# mcu.net
KiCad netlist of a schematic drawn in Altium Designer
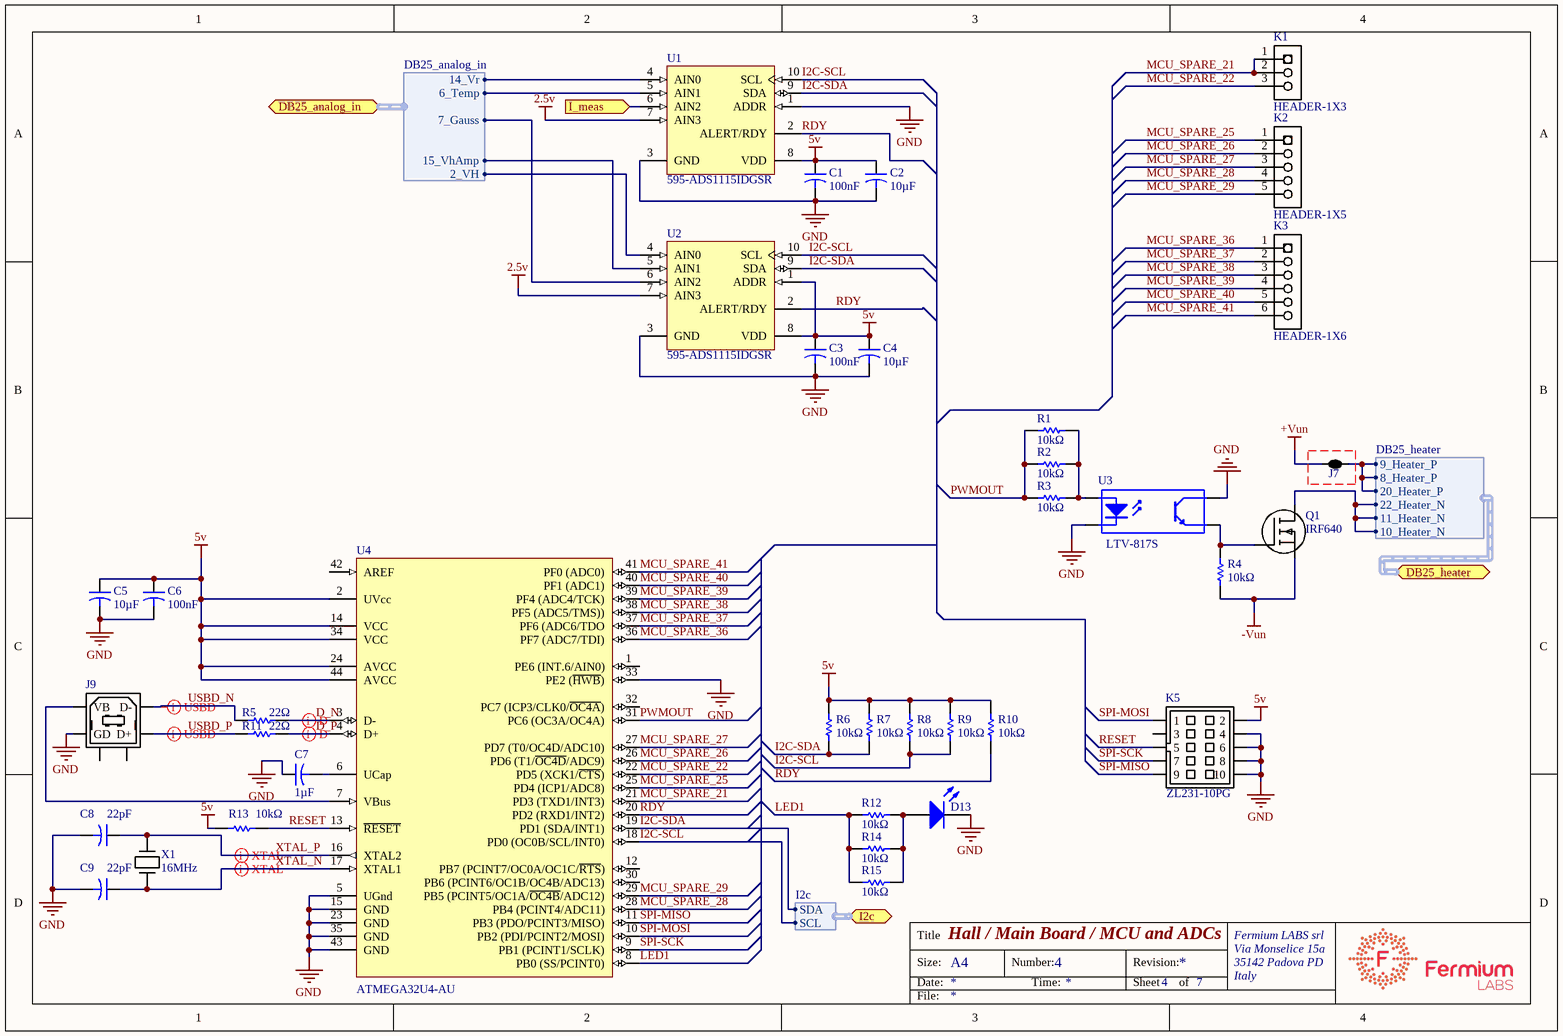
[diagram p0: mcu.SchDoc]

(export (version "E")
  (design (tool "Eeschema 10.0.6"))
  (components
    (comp (ref "C1")
      (value "~")
      (footprint "Passives:CAP 0805/2012")
      (description "Capacitor")
      (fields
        (field (name "CAPACITANCE") "100nF")
        (field (name "MANUFACTURER") "YAGEO")
        (field (name "MANUFACTURER PART NUMBER") "CC0805JRX7R9BB104")
      )
      (libsource (lib "Miscellaneous Devices") (part "Cap2"))
    )
    (comp (ref "C2")
      (value "~")
      (footprint "Passives:CAP 1206/3216")
      (description "Capacitor")
      (fields
        (field (name "MANUFACTURER") "SAMSUNG")
        (field (name "MANUFACTURER PART NUMBER") "CL31A106KAHNNNE")
        (field (name "CAPACITANCE") "10µF")
        (field (name "PUBLISHER") "Altium Limited")
      )
      (libsource (lib "Miscellaneous Devices") (part "Cap2"))
    )
    (comp (ref "C3")
      (value "~")
      (footprint "Passives:CAP 0805/2012")
      (description "Capacitor")
      (fields
        (field (name "CAPACITANCE") "100nF")
        (field (name "MANUFACTURER") "YAGEO")
        (field (name "MANUFACTURER PART NUMBER") "CC0805JRX7R9BB104")
      )
      (libsource (lib "Miscellaneous Devices") (part "Cap2"))
    )
    (comp (ref "C4")
      (value "~")
      (footprint "Passives:CAP 1206/3216")
      (description "Capacitor")
      (fields
        (field (name "MANUFACTURER") "SAMSUNG")
        (field (name "MANUFACTURER PART NUMBER") "CL31A106KAHNNNE")
        (field (name "CAPACITANCE") "10µF")
        (field (name "PUBLISHER") "Altium Limited")
      )
      (libsource (lib "Miscellaneous Devices") (part "Cap2"))
    )
    (comp (ref "C5")
      (value "~")
      (footprint "Passives:CAP 1206/3216")
      (description "Capacitor")
      (fields
        (field (name "MANUFACTURER") "SAMSUNG")
        (field (name "MANUFACTURER PART NUMBER") "CL31A106KAHNNNE")
        (field (name "CAPACITANCE") "10µF")
        (field (name "PUBLISHER") "Altium Limited")
      )
      (libsource (lib "Miscellaneous Devices") (part "Cap2"))
    )
    (comp (ref "C6")
      (value "~")
      (footprint "Passives:CAP 0805/2012")
      (description "Capacitor")
      (fields
        (field (name "CAPACITANCE") "100nF")
        (field (name "MANUFACTURER") "YAGEO")
        (field (name "MANUFACTURER PART NUMBER") "CC0805JRX7R9BB104")
      )
      (libsource (lib "Miscellaneous Devices") (part "Cap2"))
    )
    (comp (ref "C7")
      (value "~")
      (footprint "Passives:CAP 0805/2012")
      (description "Capacitor")
      (fields
        (field (name "MANUFACTURER") "SAMSUNG")
        (field (name "MANUFACTURER PART NUMBER") "CL21B105KAFNNNE")
        (field (name "CAPACITANCE") "1µF")
        (field (name "PUBLISHER") "Altium Limited")
      )
      (libsource (lib "Miscellaneous Devices") (part "Cap2"))
    )
    (comp (ref "C8")
      (value "~")
      (footprint "Passives:CAP 0805/2012")
      (description "Capacitor")
      (fields
        (field (name "MANUFACTURER") "SAMSUNG")
        (field (name "MANUFACTURER PART NUMBER") "CL21C220JBANNNC")
        (field (name "CAPACITANCE") "22pF")
        (field (name "PUBLISHER") "Altium Limited")
      )
      (libsource (lib "Miscellaneous Devices") (part "Cap2"))
    )
    (comp (ref "C9")
      (value "~")
      (footprint "Passives:CAP 0805/2012")
      (description "Capacitor")
      (fields
        (field (name "MANUFACTURER") "SAMSUNG")
        (field (name "MANUFACTURER PART NUMBER") "CL21C220JBANNNC")
        (field (name "CAPACITANCE") "22pF")
        (field (name "PUBLISHER") "Altium Limited")
      )
      (libsource (lib "Miscellaneous Devices") (part "Cap2"))
    )
    (comp (ref "D13")
      (value "~")
      (footprint "LED-0")
      (description "LED red 5mm")
      (fields
        (field (name "MANUFACTURER") "KINGBRIGHT ELECTRONIC")
        (field (name "MANUFACTURER PART NUMBER") "L-1503CB/1ID")
      )
      (libsource (lib "Miscellaneous Devices") (part "LED0"))
    )
    (comp (ref "J7")
      (value "2 way net tie junction")
      (footprint "2way_LP")
      (libsource (lib "NetTieLib") (part "2way"))
    )
    (comp (ref "J9")
      (value "~")
      (footprint "USB_TypeB")
      (description "USB b device connector")
      (fields (field (name "MANUFACTURER") "LUMBERG") (field (name "MANUFACTURER PART NUMBER") "2411 02"))
      (libsource (lib "TH Connectors") (part "USB-B"))
    )
    (comp (ref "K1")
      (value "HEADER-1X3")
      (footprint "HEADER-1X3")
      (libsource (lib "TH Connectors") (part "HEADER-1X3"))
    )
    (comp (ref "K2")
      (value "HEADER-1X5")
      (footprint "HEADER-1X5")
      (description "PINHEADER 1X5")
      (libsource (lib "TH Connectors") (part "HEADER-1X5"))
    )
    (comp (ref "K3")
      (value "HEADER-1X6")
      (footprint "HEADER-1X6")
      (libsource (lib "TH Connectors") (part "HEADER-1X6"))
    )
    (comp (ref "K5")
      (value "~")
      (footprint "IDC10-B")
      (description "header 10pin, boxed")
      (fields
        (field (name "SUPPLIER PART NUMBER 1") "ZL231-10PG")
        (field (name "MANUFACTURER") "NINIGI")
        (field (name "MANUFACTURER PART NUMBER") "ZL231-10PG")
      )
      (libsource (lib "vh_altium_library") (part "IDC10"))
    )
    (comp (ref "Q1")
      (value "IRF640")
      (footprint "vh_altium_library:DPAK-GDS")
      (description "N CHANNEL MOSFET")
      (fields (field (name "MANUFACTURER PART NUMBER") "IRF640NSPBF"))
      (libsource (lib "vh_altium_library") (part "IRLML2502"))
    )
    (comp (ref "R1")
      (value "~")
      (footprint "Passives:RES 0805/2012")
      (description "Resistor")
      (fields
        (field (name "MANUFACTURER") "YAGEO")
        (field (name "MANUFACTURER PART NUMBER") "RC0805JR-0710KL")
        (field (name "RESISTANCE") "10kΩ")
        (field (name "PUBLISHER") "Altium Limited")
      )
      (libsource (lib "Miscellaneous Devices") (part "Res1"))
    )
    (comp (ref "R2")
      (value "~")
      (footprint "Passives:RES 0805/2012")
      (description "Resistor")
      (fields
        (field (name "MANUFACTURER") "YAGEO")
        (field (name "MANUFACTURER PART NUMBER") "RC0805JR-0710KL")
        (field (name "RESISTANCE") "10kΩ")
        (field (name "PUBLISHER") "Altium Limited")
      )
      (libsource (lib "Miscellaneous Devices") (part "Res1"))
    )
    (comp (ref "R3")
      (value "~")
      (footprint "Passives:RES 0805/2012")
      (description "Resistor")
      (fields
        (field (name "MANUFACTURER") "YAGEO")
        (field (name "MANUFACTURER PART NUMBER") "RC0805JR-0710KL")
        (field (name "RESISTANCE") "10kΩ")
        (field (name "PUBLISHER") "Altium Limited")
      )
      (libsource (lib "Miscellaneous Devices") (part "Res1"))
    )
    (comp (ref "R4")
      (value "~")
      (footprint "Passives:RES 0805/2012")
      (description "Resistor")
      (fields
        (field (name "MANUFACTURER") "YAGEO")
        (field (name "MANUFACTURER PART NUMBER") "RC0805JR-0710KL")
        (field (name "RESISTANCE") "10kΩ")
        (field (name "PUBLISHER") "Altium Limited")
      )
      (libsource (lib "Miscellaneous Devices") (part "Res1"))
    )
    (comp (ref "R5")
      (value "~")
      (footprint "Passives:RES 0805/2012")
      (description "Resistor")
      (fields
        (field (name "RESISTANCE") "22Ω")
        (field (name "MANUFACTURER") "ROYAL OHM")
        (field (name "MANUFACTURER PART NUMBER") "0805S8F220JT5E")
      )
      (libsource (lib "Miscellaneous Devices") (part "Res1"))
    )
    (comp (ref "R6")
      (value "~")
      (footprint "Passives:RES 0805/2012")
      (description "Resistor")
      (fields
        (field (name "MANUFACTURER") "YAGEO")
        (field (name "MANUFACTURER PART NUMBER") "RC0805JR-0710KL")
        (field (name "RESISTANCE") "10kΩ")
        (field (name "PUBLISHER") "Altium Limited")
      )
      (libsource (lib "Miscellaneous Devices") (part "Res1"))
    )
    (comp (ref "R7")
      (value "~")
      (footprint "Passives:RES 0805/2012")
      (description "Resistor")
      (fields
        (field (name "MANUFACTURER") "YAGEO")
        (field (name "MANUFACTURER PART NUMBER") "RC0805JR-0710KL")
        (field (name "RESISTANCE") "10kΩ")
        (field (name "PUBLISHER") "Altium Limited")
      )
      (libsource (lib "Miscellaneous Devices") (part "Res1"))
    )
    (comp (ref "R8")
      (value "~")
      (footprint "Passives:RES 0805/2012")
      (description "Resistor")
      (fields
        (field (name "MANUFACTURER") "YAGEO")
        (field (name "MANUFACTURER PART NUMBER") "RC0805JR-0710KL")
        (field (name "RESISTANCE") "10kΩ")
        (field (name "PUBLISHER") "Altium Limited")
      )
      (libsource (lib "Miscellaneous Devices") (part "Res1"))
    )
    (comp (ref "R9")
      (value "~")
      (footprint "Passives:RES 0805/2012")
      (description "Resistor")
      (fields
        (field (name "MANUFACTURER") "YAGEO")
        (field (name "MANUFACTURER PART NUMBER") "RC0805JR-0710KL")
        (field (name "RESISTANCE") "10kΩ")
        (field (name "PUBLISHER") "Altium Limited")
      )
      (libsource (lib "Miscellaneous Devices") (part "Res1"))
    )
    (comp (ref "R10")
      (value "~")
      (footprint "Passives:RES 0805/2012")
      (description "Resistor")
      (fields
        (field (name "MANUFACTURER") "YAGEO")
        (field (name "MANUFACTURER PART NUMBER") "RC0805JR-0710KL")
        (field (name "RESISTANCE") "10kΩ")
        (field (name "PUBLISHER") "Altium Limited")
      )
      (libsource (lib "Miscellaneous Devices") (part "Res1"))
    )
    (comp (ref "R11")
      (value "~")
      (footprint "Passives:RES 0805/2012")
      (description "Resistor")
      (fields
        (field (name "RESISTANCE") "22Ω")
        (field (name "MANUFACTURER") "ROYAL OHM")
        (field (name "MANUFACTURER PART NUMBER") "0805S8F220JT5E")
      )
      (libsource (lib "Miscellaneous Devices") (part "Res1"))
    )
    (comp (ref "R12")
      (value "~")
      (footprint "Passives:RES 0805/2012")
      (description "Resistor")
      (fields
        (field (name "MANUFACTURER") "YAGEO")
        (field (name "MANUFACTURER PART NUMBER") "RC0805JR-0710KL")
        (field (name "RESISTANCE") "10kΩ")
        (field (name "PUBLISHER") "Altium Limited")
      )
      (libsource (lib "Miscellaneous Devices") (part "Res1"))
    )
    (comp (ref "R13")
      (value "Res1")
      (footprint "Passives:RES 0805/2012")
      (description "Resistor")
      (fields
        (field (name "MANUFACTURER") "YAGEO")
        (field (name "MANUFACTURER PART NUMBER") "RC0805JR-0710KL")
        (field (name "RESISTANCE") "10kΩ")
        (field (name "PUBLISHER") "Altium Limited")
      )
      (libsource (lib "Miscellaneous Devices") (part "Res1"))
    )
    (comp (ref "R14")
      (value "~")
      (footprint "Passives:RES 0805/2012")
      (description "Resistor")
      (fields
        (field (name "MANUFACTURER") "YAGEO")
        (field (name "MANUFACTURER PART NUMBER") "RC0805JR-0710KL")
        (field (name "RESISTANCE") "10kΩ")
        (field (name "PUBLISHER") "Altium Limited")
      )
      (libsource (lib "Miscellaneous Devices") (part "Res1"))
    )
    (comp (ref "R15")
      (value "~")
      (footprint "Passives:RES 0805/2012")
      (description "Resistor")
      (fields
        (field (name "MANUFACTURER") "YAGEO")
        (field (name "MANUFACTURER PART NUMBER") "RC0805JR-0710KL")
        (field (name "RESISTANCE") "10kΩ")
        (field (name "PUBLISHER") "Altium Limited")
      )
      (libsource (lib "Miscellaneous Devices") (part "Res1"))
    )
    (comp (ref "U1")
      (value "~")
      (footprint "TI-DGS10_N")
      (description "16-Bit 4 channel ADC with PGA and reference")
      (fields
        (field (name "SUPPLIER PART NUMBER 1") "595-ADS1115IDGSR")
        (field (name "MANUFACTURER") "Texas Instruments")
        (field (name "MANUFACTURER PART NUMBER") "ADS1115IDGSR")
      )
      (libsource (lib "TI Data Converters Analog to Digital Converter") (part "ADS1115IDGSR"))
    )
    (comp (ref "U2")
      (value "~")
      (footprint "TI-DGS10_N")
      (description "16-Bit 4 channel ADC with PGA and reference")
      (fields
        (field (name "SUPPLIER PART NUMBER 1") "595-ADS1115IDGSR")
        (field (name "MANUFACTURER") "Texas Instruments")
        (field (name "MANUFACTURER PART NUMBER") "ADS1115IDGSR")
      )
      (libsource (lib "TI Data Converters Analog to Digital Converter") (part "ADS1115IDGSR"))
    )
    (comp (ref "U3")
      (value "LTV-817")
      (footprint "custom_components:gullwing-opto-4")
      (description "4-Pin Phototransistor Optocoupler")
      (fields
        (field (name "SUPPLIER PART NUMBER 1") "LTV-817S")
        (field (name "MANUFACTURER") "LITEON")
        (field (name "MANUFACTURER PART NUMBER") "LTV-817S")
        (field (name "PUBLISHER") "Altium Limited")
      )
      (libsource (lib "Miscellaneous Devices") (part "Optoisolator1"))
    )
    (comp (ref "U4")
      (value "~")
      (footprint "44ML_N")
      (description "8-bit AVR MCU, 16MHz, 32KB Flash, 1KB EEPROM, 2.5KB SRAM, USB")
      (fields (field (name "MANUFACTURER") "ATMEL") (field (name "MANUFACTURER PART NUMBER") "ATMEGA32U4-AU"))
      (libsource (lib "Atmel Microcontroller megaAVR") (part "ATmega32U4-AU"))
    )
    (comp (ref "X1")
      (value "~")
      (footprint "ABRACON ABLS")
      (description "quartz crystal")
      (fields
        (field (name "MANUFACTURER") "YIC")
        (field (name "FREQUENCY") "16MHz")
        (field (name "POWER") "1mW")
      )
      (libsource (lib "vh_altium_library") (part "CRYSTAL-GENERIC"))
    )
  )
  (nets
    (net (code "4") (name "+Vun") (class "Default")
      (node (ref "J7") (pin "1") (pinfunction "1_1") (pintype "passive"))
    )
    (net (code "5") (name "-Vun") (class "Default")
      (node (ref "Q1") (pin "S") (pintype "passive"))
      (node (ref "R4") (pin "1") (pinfunction "1_1") (pintype "passive"))
    )
    (net (code "6") (name "/2_VH") (class "Default")
      (node (ref "U2") (pin "4") (pinfunction "AIN0_4") (pintype "input"))
    )
    (net (code "7") (name "/6_Temp") (class "Default")
      (node (ref "U1") (pin "5") (pinfunction "AIN1_5") (pintype "input"))
    )
    (net (code "8") (name "/7_Gauss") (class "Default")
      (node (ref "U2") (pin "6") (pinfunction "AIN2_6") (pintype "input"))
    )
    (net (code "9") (name "/10_Heater_N") (class "Default") (node (ref "Q1") (pin "D") (pintype "passive")))
    (net (code "10") (name "/14_Vr") (class "Default")
      (node (ref "U1") (pin "4") (pinfunction "AIN0_4") (pintype "input"))
    )
    (net (code "11") (name "/15_VhAmp") (class "Default")
      (node (ref "U2") (pin "5") (pinfunction "AIN1_5") (pintype "input"))
    )
    (net (code "12") (name "/20_Heater_P") (class "Default")
      (node (ref "J7") (pin "2") (pinfunction "2_2") (pintype "passive"))
    )
    (net (code "13") (name "/D_N") (class "Default")
      (node (ref "R5") (pin "1") (pinfunction "1_1") (pintype "passive"))
      (node (ref "U4") (pin "3") (pinfunction "D-_3") (pintype "bidirectional"))
    )
    (net (code "14") (name "/D_P") (class "Default")
      (node (ref "R11") (pin "1") (pinfunction "1_1") (pintype "passive"))
      (node (ref "U4") (pin "4") (pinfunction "D+_4") (pintype "bidirectional"))
    )
    (net (code "15") (name "/I2C-SCL") (class "Default")
      (node (ref "R8") (pin "1") (pinfunction "1_1") (pintype "passive"))
      (node (ref "R9") (pin "1") (pinfunction "1_1") (pintype "passive"))
      (node (ref "U1") (pin "10") (pinfunction "SCL_10") (pintype "input"))
      (node (ref "U2") (pin "10") (pinfunction "SCL_10") (pintype "input"))
      (node (ref "U4") (pin "18") (pinfunction "PD0_(OC0B/SCL/INT0)_18") (pintype "bidirectional"))
    )
    (net (code "16") (name "/I2C-SDA") (class "Default")
      (node (ref "R6") (pin "1") (pinfunction "1_1") (pintype "passive"))
      (node (ref "R7") (pin "1") (pinfunction "1_1") (pintype "passive"))
      (node (ref "U1") (pin "9") (pinfunction "SDA_9") (pintype "bidirectional"))
      (node (ref "U2") (pin "9") (pinfunction "SDA_9") (pintype "bidirectional"))
      (node (ref "U4") (pin "19") (pinfunction "PD1_(SDA/INT1)_19") (pintype "bidirectional"))
    )
    (net (code "17") (name "/I_meas") (class "Default")
      (node (ref "U1") (pin "6") (pinfunction "AIN2_6") (pintype "input"))
    )
    (net (code "18") (name "/LED1") (class "Default")
      (node (ref "R12") (pin "2") (pinfunction "2_2") (pintype "passive"))
      (node (ref "R14") (pin "2") (pinfunction "2_2") (pintype "passive"))
      (node (ref "R15") (pin "2") (pinfunction "2_2") (pintype "passive"))
      (node (ref "U4") (pin "8") (pinfunction "PB0_(SS/PCINT0)_8") (pintype "bidirectional"))
    )
    (net (code "19") (name "/MCU_SPARE_21") (class "Default")
      (node (ref "K1") (pin "1") (pintype "passive"))
      (node (ref "K1") (pin "2") (pintype "passive"))
      (node (ref "U4") (pin "21") (pinfunction "PD3_(TXD1/INT3)_21") (pintype "bidirectional"))
    )
    (net (code "20") (name "/MCU_SPARE_22") (class "Default")
      (node (ref "K1") (pin "3") (pintype "passive"))
      (node (ref "U4") (pin "22") (pinfunction "PD5_(XCK1/~{CTS})_22") (pintype "bidirectional"))
    )
    (net (code "21") (name "/MCU_SPARE_25") (class "Default")
      (node (ref "K2") (pin "1") (pintype "passive"))
      (node (ref "U4") (pin "25") (pinfunction "PD4_(ICP1/ADC8)_25") (pintype "bidirectional"))
    )
    (net (code "22") (name "/MCU_SPARE_26") (class "Default")
      (node (ref "K2") (pin "2") (pintype "passive"))
      (node (ref "U4") (pin "26") (pinfunction "PD6_(T1/~{OC4D}/ADC9)_26") (pintype "bidirectional"))
    )
    (net (code "23") (name "/MCU_SPARE_27") (class "Default")
      (node (ref "K2") (pin "3") (pintype "passive"))
      (node (ref "U4") (pin "27") (pinfunction "PD7_(T0/OC4D/ADC10)_27") (pintype "bidirectional"))
    )
    (net (code "24") (name "/MCU_SPARE_28") (class "Default")
      (node (ref "K2") (pin "4") (pintype "passive"))
      (node (ref "U4") (pin "28") (pinfunction "PB4_(PCINT4/ADC11)_28") (pintype "bidirectional"))
    )
    (net (code "25") (name "/MCU_SPARE_29") (class "Default")
      (node (ref "K2") (pin "5") (pintype "passive"))
      (node (ref "U4") (pin "29") (pinfunction "PB5_(PCINT5/OC1A/~{OC4B}/ADC12)_29") (pintype "bidirectional"))
    )
    (net (code "26") (name "/MCU_SPARE_36") (class "Default")
      (node (ref "K3") (pin "1") (pintype "passive"))
      (node (ref "U4") (pin "36") (pinfunction "PF7_(ADC7/TDI)_36") (pintype "bidirectional"))
    )
    (net (code "27") (name "/MCU_SPARE_37") (class "Default")
      (node (ref "K3") (pin "2") (pintype "passive"))
      (node (ref "U4") (pin "37") (pinfunction "PF6_(ADC6/TDO_37") (pintype "bidirectional"))
    )
    (net (code "28") (name "/MCU_SPARE_38") (class "Default")
      (node (ref "K3") (pin "3") (pintype "passive"))
      (node (ref "U4") (pin "38") (pinfunction "PF5_(ADC5/TMS))_38") (pintype "bidirectional"))
    )
    (net (code "29") (name "/MCU_SPARE_39") (class "Default")
      (node (ref "K3") (pin "4") (pintype "passive"))
      (node (ref "U4") (pin "39") (pinfunction "PF4_(ADC4/TCK)_39") (pintype "bidirectional"))
    )
    (net (code "30") (name "/MCU_SPARE_40") (class "Default")
      (node (ref "K3") (pin "5") (pintype "passive"))
      (node (ref "U4") (pin "40") (pinfunction "PF1_(ADC1)_40") (pintype "bidirectional"))
    )
    (net (code "31") (name "/MCU_SPARE_41") (class "Default")
      (node (ref "K3") (pin "6") (pintype "passive"))
      (node (ref "U4") (pin "41") (pinfunction "PF0_(ADC0)_41") (pintype "bidirectional"))
    )
    (net (code "32") (name "/PWMOUT") (class "Default")
      (node (ref "R1") (pin "2") (pinfunction "2_2") (pintype "passive"))
      (node (ref "R2") (pin "2") (pinfunction "2_2") (pintype "passive"))
      (node (ref "R3") (pin "2") (pinfunction "2_2") (pintype "passive"))
      (node (ref "U4") (pin "31") (pinfunction "PC6_(OC3A/OC4A)_31") (pintype "bidirectional"))
    )
    (net (code "33") (name "/RDY") (class "Default")
      (node (ref "R10") (pin "1") (pinfunction "1_1") (pintype "passive"))
      (node (ref "U1") (pin "2") (pinfunction "ALERT/RDY_2") (pintype "open_collector"))
      (node (ref "U2") (pin "2") (pinfunction "ALERT/RDY_2") (pintype "open_collector"))
      (node (ref "U4") (pin "20") (pinfunction "PD2_(RXD1/INT2)_20") (pintype "bidirectional"))
    )
    (net (code "34") (name "/RESET") (class "Default")
      (node (ref "K5") (pin "5") (pinfunction "5_5") (pintype "passive"))
      (node (ref "R13") (pin "1") (pinfunction "1_1") (pintype "passive"))
      (node (ref "U4") (pin "13") (pinfunction "~{RESET}_13") (pintype "input"))
    )
    (net (code "35") (name "/SPI-MISO") (class "Default")
      (node (ref "K5") (pin "9") (pinfunction "9_9") (pintype "passive"))
      (node (ref "U4") (pin "11") (pinfunction "PB3_(PDO/PCINT3/MISO)_11") (pintype "bidirectional"))
    )
    (net (code "36") (name "/SPI-MOSI") (class "Default")
      (node (ref "K5") (pin "1") (pinfunction "1_1") (pintype "passive"))
      (node (ref "U4") (pin "10") (pinfunction "PB2_(PDI/PCINT2/MOSI)_10") (pintype "bidirectional"))
    )
    (net (code "37") (name "/SPI-SCK") (class "Default")
      (node (ref "K5") (pin "7") (pinfunction "7_7") (pintype "passive"))
      (node (ref "U4") (pin "9") (pinfunction "PB1_(PCINT1/SCLK)_9") (pintype "bidirectional"))
    )
    (net (code "38") (name "/USBD_N") (class "Default")
      (node (ref "J9") (pin "2") (pinfunction "D-_2") (pintype "passive"))
      (node (ref "R5") (pin "2") (pinfunction "2_2") (pintype "passive"))
    )
    (net (code "39") (name "/USBD_P") (class "Default")
      (node (ref "J9") (pin "3") (pinfunction "D+_3") (pintype "passive"))
      (node (ref "R11") (pin "2") (pinfunction "2_2") (pintype "passive"))
    )
    (net (code "40") (name "/XTAL_N") (class "Default")
      (node (ref "C9") (pin "1") (pinfunction "1_1") (pintype "passive"))
      (node (ref "U4") (pin "17") (pinfunction "XTAL1_17") (pintype "input"))
      (node (ref "X1") (pin "2") (pintype "passive"))
    )
    (net (code "41") (name "/XTAL_P") (class "Default")
      (node (ref "C8") (pin "1") (pinfunction "1_1") (pintype "passive"))
      (node (ref "U4") (pin "16") (pinfunction "XTAL2_16") (pintype "output"))
      (node (ref "X1") (pin "1") (pintype "passive"))
    )
    (net (code "45") (name "2.5v") (class "Default")
      (node (ref "U1") (pin "7") (pinfunction "AIN3_7") (pintype "input"))
      (node (ref "U2") (pin "7") (pinfunction "AIN3_7") (pintype "input"))
    )
    (net (code "46") (name "5v") (class "Default")
      (node (ref "C1") (pin "1") (pinfunction "1_1") (pintype "passive"))
      (node (ref "C2") (pin "1") (pinfunction "1_1") (pintype "passive"))
      (node (ref "C3") (pin "1") (pinfunction "1_1") (pintype "passive"))
      (node (ref "C4") (pin "1") (pinfunction "1_1") (pintype "passive"))
      (node (ref "C5") (pin "1") (pinfunction "1_1") (pintype "passive"))
      (node (ref "C6") (pin "1") (pinfunction "1_1") (pintype "passive"))
      (node (ref "K5") (pin "2") (pinfunction "2_2") (pintype "passive"))
      (node (ref "R10") (pin "2") (pinfunction "2_2") (pintype "passive"))
      (node (ref "R13") (pin "2") (pinfunction "2_2") (pintype "passive"))
      (node (ref "R6") (pin "2") (pinfunction "2_2") (pintype "passive"))
      (node (ref "R7") (pin "2") (pinfunction "2_2") (pintype "passive"))
      (node (ref "R8") (pin "2") (pinfunction "2_2") (pintype "passive"))
      (node (ref "R9") (pin "2") (pinfunction "2_2") (pintype "passive"))
      (node (ref "U1") (pin "8") (pinfunction "VDD_8") (pintype "power_in"))
      (node (ref "U2") (pin "1") (pinfunction "ADDR_1") (pintype "input"))
      (node (ref "U2") (pin "8") (pinfunction "VDD_8") (pintype "power_in"))
      (node (ref "U4") (pin "14") (pinfunction "VCC_14") (pintype "power_in"))
      (node (ref "U4") (pin "2") (pinfunction "UVcc_2") (pintype "power_in"))
      (node (ref "U4") (pin "24") (pinfunction "AVCC_24") (pintype "power_in"))
      (node (ref "U4") (pin "34") (pinfunction "VCC_34") (pintype "power_in"))
      (node (ref "U4") (pin "44") (pinfunction "AVCC_44") (pintype "power_in"))
    )
    (net (code "47") (name "GND") (class "Default")
      (node (ref "C1") (pin "2") (pinfunction "2_2") (pintype "passive"))
      (node (ref "C2") (pin "2") (pinfunction "2_2") (pintype "passive"))
      (node (ref "C3") (pin "2") (pinfunction "2_2") (pintype "passive"))
      (node (ref "C4") (pin "2") (pinfunction "2_2") (pintype "passive"))
      (node (ref "C5") (pin "2") (pinfunction "2_2") (pintype "passive"))
      (node (ref "C6") (pin "2") (pinfunction "2_2") (pintype "passive"))
      (node (ref "C7") (pin "1") (pinfunction "1_1") (pintype "passive"))
      (node (ref "C8") (pin "2") (pinfunction "2_2") (pintype "passive"))
      (node (ref "C9") (pin "2") (pinfunction "2_2") (pintype "passive"))
      (node (ref "D13") (pin "1") (pinfunction "K_1") (pintype "passive"))
      (node (ref "J9") (pin "4") (pinfunction "GD_4") (pintype "passive"))
      (node (ref "K5") (pin "10") (pinfunction "10_10") (pintype "passive"))
      (node (ref "K5") (pin "4") (pinfunction "4_4") (pintype "passive"))
      (node (ref "K5") (pin "6") (pinfunction "6_6") (pintype "passive"))
      (node (ref "K5") (pin "8") (pinfunction "8_8") (pintype "passive"))
      (node (ref "U1") (pin "1") (pinfunction "ADDR_1") (pintype "input"))
      (node (ref "U1") (pin "3") (pinfunction "GND_3") (pintype "power_in"))
      (node (ref "U2") (pin "3") (pinfunction "GND_3") (pintype "power_in"))
      (node (ref "U3") (pin "2") (pinfunction "K_2") (pintype "passive"))
      (node (ref "U3") (pin "4") (pinfunction "C_4") (pintype "passive"))
      (node (ref "U4") (pin "15") (pinfunction "GND_15") (pintype "power_in"))
      (node (ref "U4") (pin "23") (pinfunction "GND_23") (pintype "power_in"))
      (node (ref "U4") (pin "33") (pinfunction "PE2_(~{HWB})_33") (pintype "bidirectional"))
      (node (ref "U4") (pin "35") (pinfunction "GND_35") (pintype "power_in"))
      (node (ref "U4") (pin "43") (pinfunction "GND_43") (pintype "power_in"))
      (node (ref "U4") (pin "5") (pinfunction "UGnd_5") (pintype "power_in"))
    )
    (net (code "48") (name "Net-(D13-A)") (class "Default")
      (node (ref "D13") (pin "2") (pinfunction "A_2") (pintype "passive"))
      (node (ref "R12") (pin "1") (pinfunction "1_1") (pintype "passive"))
      (node (ref "R14") (pin "1") (pinfunction "1_1") (pintype "passive"))
      (node (ref "R15") (pin "1") (pinfunction "1_1") (pintype "passive"))
    )
    (net (code "49") (name "Net-(J9-VB)") (class "Default")
      (node (ref "J9") (pin "1") (pinfunction "VB_1") (pintype "passive"))
      (node (ref "U4") (pin "7") (pinfunction "VBus_7") (pintype "input"))
    )
    (net (code "50") (name "Net-(U3-A)") (class "Default")
      (node (ref "R1") (pin "1") (pinfunction "1_1") (pintype "passive"))
      (node (ref "R2") (pin "1") (pinfunction "1_1") (pintype "passive"))
      (node (ref "R3") (pin "1") (pinfunction "1_1") (pintype "passive"))
      (node (ref "U3") (pin "1") (pinfunction "A_1") (pintype "passive"))
    )
    (net (code "51") (name "Net-(U3-E)") (class "Default")
      (node (ref "Q1") (pin "G") (pintype "passive"))
      (node (ref "R4") (pin "2") (pinfunction "2_2") (pintype "passive"))
      (node (ref "U3") (pin "3") (pinfunction "E_3") (pintype "passive"))
    )
    (net (code "52") (name "Net-(U4-UCap)") (class "Default")
      (node (ref "C7") (pin "2") (pinfunction "2_2") (pintype "passive"))
      (node (ref "U4") (pin "6") (pinfunction "UCap_6") (pintype "passive"))
    )
    (net (code "53") (name "unconnected-(J9-Pad5)") (class "Default")
      (node (ref "J9") (pin "5") (pintype "passive"))
    )
    (net (code "54") (name "unconnected-(J9-Pad6)") (class "Default")
      (node (ref "J9") (pin "6") (pintype "passive"))
    )
    (net (code "55") (name "unconnected-(K5-Pad3)") (class "Default")
      (node (ref "K5") (pin "3") (pinfunction "3_3") (pintype "passive"))
    )
    (net (code "56") (name "unconnected-(U4-AREF-Pad42)") (class "Default")
      (node (ref "U4") (pin "42") (pinfunction "AREF_42") (pintype "input"))
    )
    (net (code "57") (name "unconnected-(U4-PB6_(PCINT6{slash}OC1B{slash}OC4B{slash}ADC13)-Pad30)") (class "Default")
      (node (ref "U4") (pin "30") (pinfunction "PB6_(PCINT6/OC1B/OC4B/ADC13)_30") (pintype "bidirectional"))
    )
    (net (code "58") (name "unconnected-(U4-PB7_(PCINT7{slash}OC0A{slash}OC1C{slash}~{RTS})-Pad12)") (class "Default")
      (node (ref "U4") (pin "12") (pinfunction "PB7_(PCINT7/OC0A/OC1C/~{RTS})_12") (pintype "bidirectional"))
    )
    (net (code "59") (name "unconnected-(U4-PC7_(ICP3{slash}CLK0{slash}~{OC4A})-Pad32)") (class "Default")
      (node (ref "U4") (pin "32") (pinfunction "PC7_(ICP3/CLK0/~{OC4A})_32") (pintype "bidirectional"))
    )
    (net (code "60") (name "unconnected-(U4-PE6_(INT.6{slash}AIN0)-Pad1)") (class "Default")
      (node (ref "U4") (pin "1") (pinfunction "PE6_(INT.6/AIN0)_1") (pintype "bidirectional"))
    )
  )
)
